# rpiInterface2.net
KiCad netlist of a schematic drawn in EAGLE
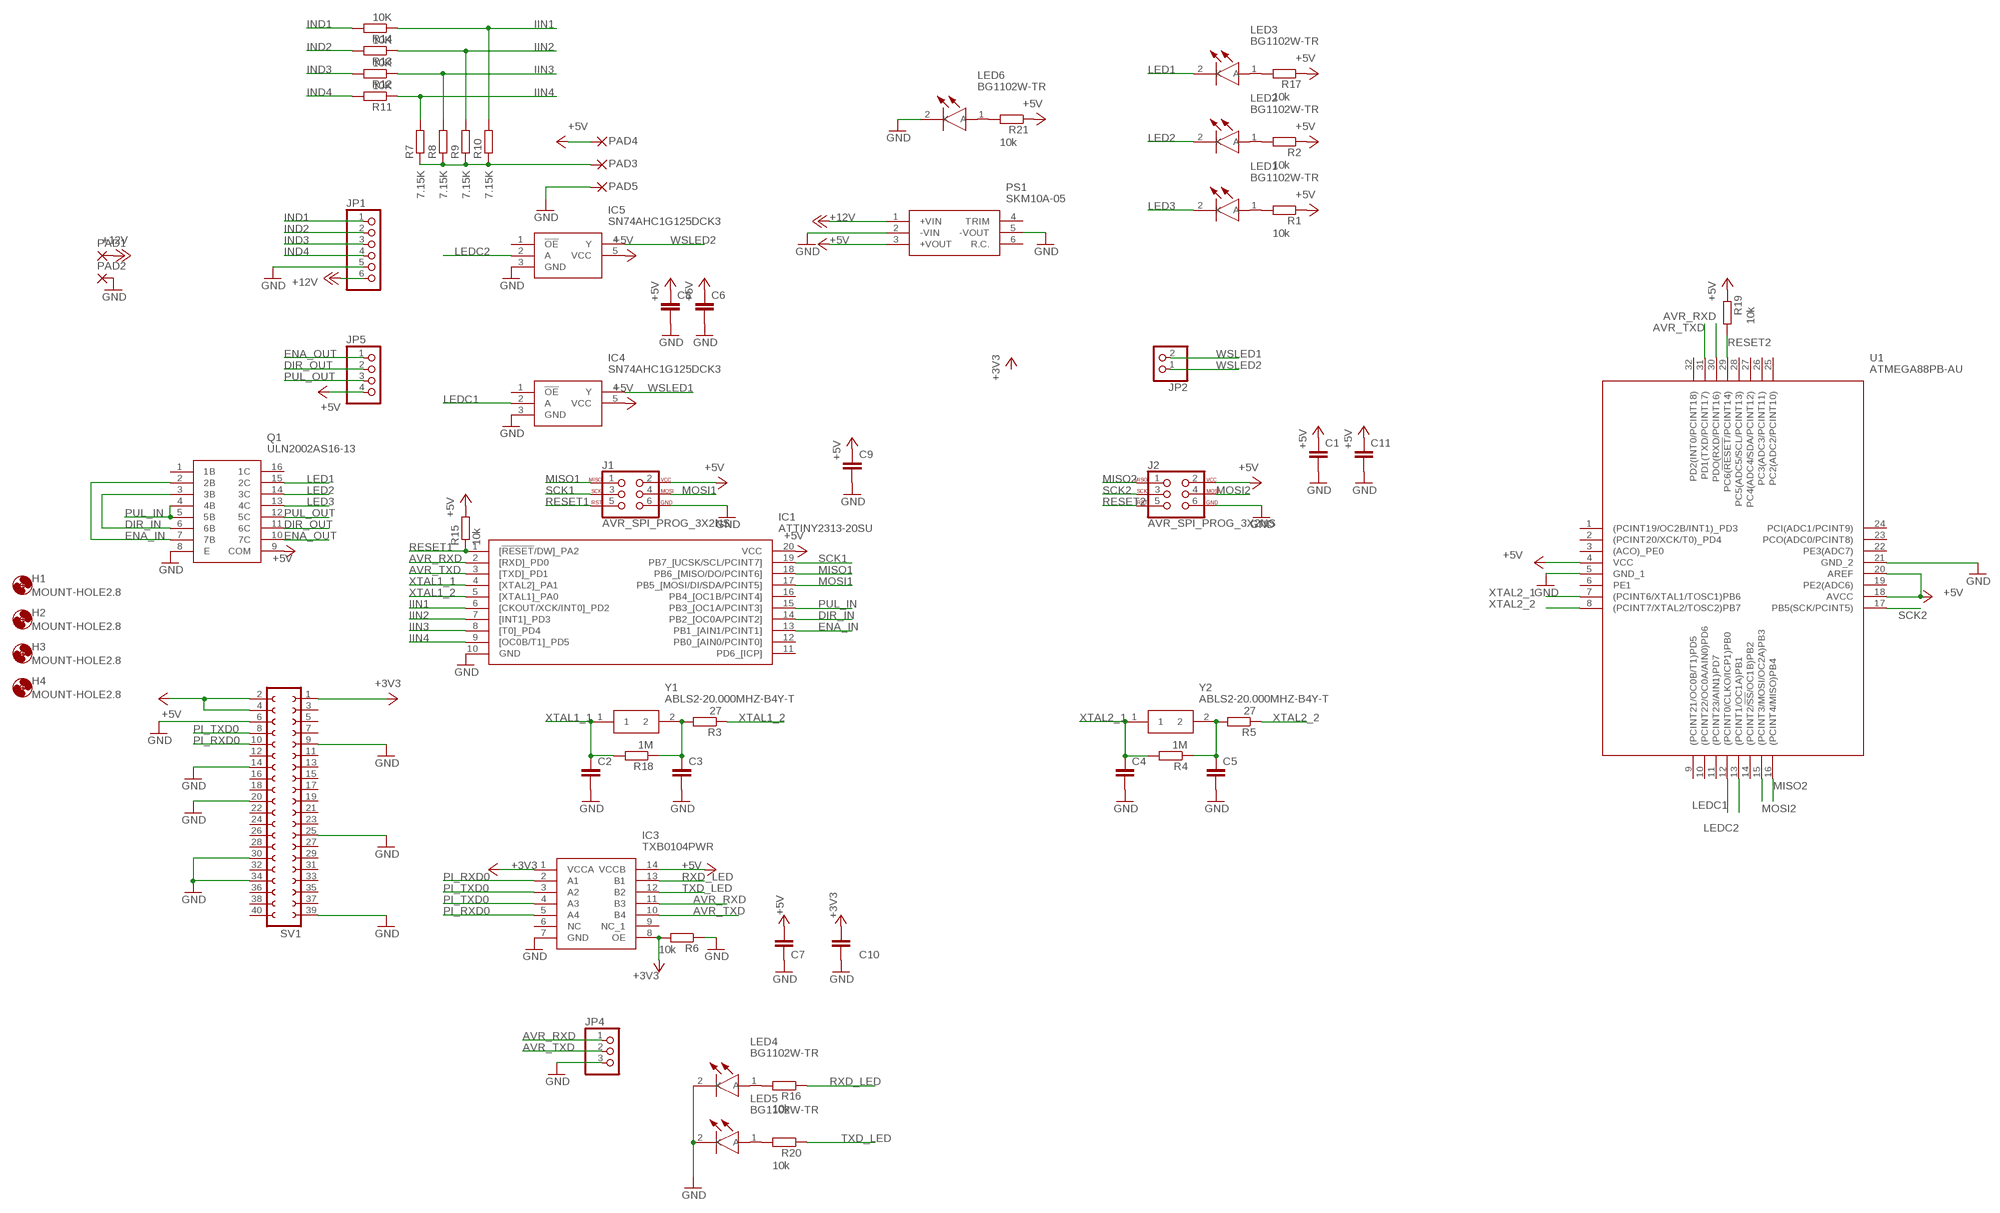
[diagram p0: schematic, sheet 1]

(export (version "E")
  (design (tool "Eeschema 10.0.6"))
  (components
    (comp (ref "C1")
      (value "C-EUC1206")
      (footprint "eagle-import:C1206")
      (libsource (lib "eagle-import") (part "C-EUC1206"))
    )
    (comp (ref "C2")
      (value "C-EUC1206")
      (footprint "eagle-import:C1206")
      (libsource (lib "eagle-import") (part "C-EUC1206"))
    )
    (comp (ref "C3")
      (value "C-EUC1206")
      (footprint "eagle-import:C1206")
      (libsource (lib "eagle-import") (part "C-EUC1206"))
    )
    (comp (ref "C4")
      (value "C-EUC1206")
      (footprint "eagle-import:C1206")
      (libsource (lib "eagle-import") (part "C-EUC1206"))
    )
    (comp (ref "C5")
      (value "C-EUC1206")
      (footprint "eagle-import:C1206")
      (libsource (lib "eagle-import") (part "C-EUC1206"))
    )
    (comp (ref "C6")
      (value "C-EUC1206")
      (footprint "eagle-import:C1206")
      (libsource (lib "eagle-import") (part "C-EUC1206"))
    )
    (comp (ref "C7")
      (value "C-EUC1206")
      (footprint "eagle-import:C1206")
      (libsource (lib "eagle-import") (part "C-EUC1206"))
    )
    (comp (ref "C8")
      (value "C-EUC1206")
      (footprint "eagle-import:C1206")
      (libsource (lib "eagle-import") (part "C-EUC1206"))
    )
    (comp (ref "C9")
      (value "C-EUC1206")
      (footprint "eagle-import:C1206")
      (libsource (lib "eagle-import") (part "C-EUC1206"))
    )
    (comp (ref "C10")
      (value "C-EUC1206")
      (footprint "eagle-import:C1206")
      (libsource (lib "eagle-import") (part "C-EUC1206"))
    )
    (comp (ref "C11")
      (value "C-EUC1206")
      (footprint "eagle-import:C1206")
      (libsource (lib "eagle-import") (part "C-EUC1206"))
    )
    (comp (ref "H1")
      (value "MOUNT-HOLE2.8")
      (footprint "eagle-import:2,8")
      (libsource (lib "eagle-import") (part "MOUNT-HOLE2.8"))
    )
    (comp (ref "H2")
      (value "MOUNT-HOLE2.8")
      (footprint "eagle-import:2,8")
      (libsource (lib "eagle-import") (part "MOUNT-HOLE2.8"))
    )
    (comp (ref "H3")
      (value "MOUNT-HOLE2.8")
      (footprint "eagle-import:2,8")
      (libsource (lib "eagle-import") (part "MOUNT-HOLE2.8"))
    )
    (comp (ref "H4")
      (value "MOUNT-HOLE2.8")
      (footprint "eagle-import:2,8")
      (libsource (lib "eagle-import") (part "MOUNT-HOLE2.8"))
    )
    (comp (ref "IC1")
      (value "ATTINY2313-20SU")
      (footprint "eagle-import:SOIC127P1032X265-20N")
      (fields (field (name "MOUSER_PART_NUMBER") "556-ATTINY2313-20SU"))
      (libsource (lib "eagle-import") (part "ATTINY2313-20SU"))
    )
    (comp (ref "IC3")
      (value "TXB0104PWR")
      (footprint "eagle-import:SOP65P640X120-14N")
      (fields (field (name "MOUSER_PART_NUMBER") "595-TXB0104PWR"))
      (libsource (lib "eagle-import") (part "TXB0104PWR"))
    )
    (comp (ref "IC4")
      (value "SN74AHC1G125DCK3")
      (footprint "eagle-import:SOT65P210X110-5N")
      (fields (field (name "MOUSER_PART_NUMBER") "595-SN74AHC1G125DCK3"))
      (libsource (lib "eagle-import") (part "SN74AHC1G125DCK3"))
    )
    (comp (ref "IC5")
      (value "SN74AHC1G125DCK3")
      (footprint "eagle-import:SOT65P210X110-5N")
      (fields (field (name "MOUSER_PART_NUMBER") "595-SN74AHC1G125DCK3"))
      (libsource (lib "eagle-import") (part "SN74AHC1G125DCK3"))
    )
    (comp (ref "J1")
      (value "AVR_SPI_PROG_3X2NS")
      (footprint "eagle-import:2X3-NS")
      (libsource (lib "eagle-import") (part "AVR_SPI_PROG_3X2NS"))
    )
    (comp (ref "J2")
      (value "AVR_SPI_PROG_3X2NS")
      (footprint "eagle-import:2X3-NS")
      (libsource (lib "eagle-import") (part "AVR_SPI_PROG_3X2NS"))
    )
    (comp (ref "JP1")
      (value "PINHD-1X6")
      (footprint "eagle-import:1X06")
      (libsource (lib "eagle-import") (part "PINHD-1X6"))
    )
    (comp (ref "JP2")
      (value "PINHD-1X2")
      (footprint "eagle-import:1X02")
      (libsource (lib "eagle-import") (part "PINHD-1X2"))
    )
    (comp (ref "JP4")
      (value "PINHD-1X3")
      (footprint "eagle-import:1X03")
      (libsource (lib "eagle-import") (part "PINHD-1X3"))
    )
    (comp (ref "JP5")
      (value "PINHD-1X4")
      (footprint "eagle-import:1X04")
      (libsource (lib "eagle-import") (part "PINHD-1X4"))
    )
    (comp (ref "LED1")
      (value "BG1102W-TR")
      (footprint "eagle-import:BG1102WTR")
      (fields (field (name "MOUSER_PART_NUMBER") "327-BG1102WTR"))
      (libsource (lib "eagle-import") (part "BG1102W-TR"))
    )
    (comp (ref "LED2")
      (value "BG1102W-TR")
      (footprint "eagle-import:BG1102WTR")
      (fields (field (name "MOUSER_PART_NUMBER") "327-BG1102WTR"))
      (libsource (lib "eagle-import") (part "BG1102W-TR"))
    )
    (comp (ref "LED3")
      (value "BG1102W-TR")
      (footprint "eagle-import:BG1102WTR")
      (fields (field (name "MOUSER_PART_NUMBER") "327-BG1102WTR"))
      (libsource (lib "eagle-import") (part "BG1102W-TR"))
    )
    (comp (ref "LED4")
      (value "BG1102W-TR")
      (footprint "eagle-import:BG1102WTR")
      (fields (field (name "MOUSER_PART_NUMBER") "327-BG1102WTR"))
      (libsource (lib "eagle-import") (part "BG1102W-TR"))
    )
    (comp (ref "LED5")
      (value "BG1102W-TR")
      (footprint "eagle-import:BG1102WTR")
      (fields (field (name "MOUSER_PART_NUMBER") "327-BG1102WTR"))
      (libsource (lib "eagle-import") (part "BG1102W-TR"))
    )
    (comp (ref "LED6")
      (value "BG1102W-TR")
      (footprint "eagle-import:BG1102WTR")
      (fields (field (name "MOUSER_PART_NUMBER") "327-BG1102WTR"))
      (libsource (lib "eagle-import") (part "BG1102W-TR"))
    )
    (comp (ref "PAD1")
      (value "3,17/1,3")
      (footprint "eagle-import:3,17_1,3")
      (libsource (lib "eagle-import") (part "3,17/1,3"))
    )
    (comp (ref "PAD2")
      (value "3,17/1,3")
      (footprint "eagle-import:3,17_1,3")
      (libsource (lib "eagle-import") (part "3,17/1,3"))
    )
    (comp (ref "PAD3")
      (value "SMD2")
      (footprint "eagle-import:SMD1,27-2,54")
      (libsource (lib "eagle-import") (part "SMD2"))
    )
    (comp (ref "PAD4")
      (value "SMD2")
      (footprint "eagle-import:SMD1,27-2,54")
      (libsource (lib "eagle-import") (part "SMD2"))
    )
    (comp (ref "PAD5")
      (value "SMD2")
      (footprint "eagle-import:SMD1,27-2,54")
      (libsource (lib "eagle-import") (part "SMD2"))
    )
    (comp (ref "PS1")
      (value "SKM10A-05")
      (footprint "eagle-import:SKM10A05")
      (fields (field (name "MOUSER_PART_NUMBER") "709-SKM10A-05"))
      (libsource (lib "eagle-import") (part "SKM10A-05"))
    )
    (comp (ref "Q1")
      (value "ULN2002AS16-13")
      (footprint "eagle-import:SOIC127P605X126-16N")
      (fields (field (name "MOUSER_PART_NUMBER") "621-ULN2002AS16-13"))
      (libsource (lib "eagle-import") (part "ULN2002AS16-13"))
    )
    (comp (ref "R1")
      (value "10k")
      (footprint "eagle-import:R1206")
      (libsource (lib "eagle-import") (part "R-EU_R1206"))
    )
    (comp (ref "R2")
      (value "10k")
      (footprint "eagle-import:R1206")
      (libsource (lib "eagle-import") (part "R-EU_R1206"))
    )
    (comp (ref "R3")
      (value "27")
      (footprint "eagle-import:R1206")
      (libsource (lib "eagle-import") (part "R-EU_R1206"))
    )
    (comp (ref "R4")
      (value "1M")
      (footprint "eagle-import:R1206")
      (libsource (lib "eagle-import") (part "R-EU_R1206"))
    )
    (comp (ref "R5")
      (value "27")
      (footprint "eagle-import:R1206")
      (libsource (lib "eagle-import") (part "R-EU_R1206"))
    )
    (comp (ref "R6")
      (value "10k")
      (footprint "eagle-import:R1206")
      (libsource (lib "eagle-import") (part "R-EU_R1206"))
    )
    (comp (ref "R7")
      (value "7.15K")
      (footprint "eagle-import:R1206")
      (libsource (lib "eagle-import") (part "R-EU_R1206"))
    )
    (comp (ref "R8")
      (value "7.15K")
      (footprint "eagle-import:R1206")
      (libsource (lib "eagle-import") (part "R-EU_R1206"))
    )
    (comp (ref "R9")
      (value "7.15K")
      (footprint "eagle-import:R1206")
      (libsource (lib "eagle-import") (part "R-EU_R1206"))
    )
    (comp (ref "R10")
      (value "7.15K")
      (footprint "eagle-import:R1206")
      (libsource (lib "eagle-import") (part "R-EU_R1206"))
    )
    (comp (ref "R11")
      (value "10K")
      (footprint "eagle-import:R1206")
      (libsource (lib "eagle-import") (part "R-EU_R1206"))
    )
    (comp (ref "R12")
      (value "10K")
      (footprint "eagle-import:R1206")
      (libsource (lib "eagle-import") (part "R-EU_R1206"))
    )
    (comp (ref "R13")
      (value "10K")
      (footprint "eagle-import:R1206")
      (libsource (lib "eagle-import") (part "R-EU_R1206"))
    )
    (comp (ref "R14")
      (value "10K")
      (footprint "eagle-import:R1206")
      (libsource (lib "eagle-import") (part "R-EU_R1206"))
    )
    (comp (ref "R15")
      (value "10k")
      (footprint "eagle-import:R1206")
      (libsource (lib "eagle-import") (part "R-EU_R1206"))
    )
    (comp (ref "R16")
      (value "10k")
      (footprint "eagle-import:R1206")
      (libsource (lib "eagle-import") (part "R-EU_R1206"))
    )
    (comp (ref "R17")
      (value "10k")
      (footprint "eagle-import:R1206")
      (libsource (lib "eagle-import") (part "R-EU_R1206"))
    )
    (comp (ref "R18")
      (value "1M")
      (footprint "eagle-import:R1206")
      (libsource (lib "eagle-import") (part "R-EU_R1206"))
    )
    (comp (ref "R19")
      (value "10k")
      (footprint "eagle-import:R1206")
      (libsource (lib "eagle-import") (part "R-EU_R1206"))
    )
    (comp (ref "R20")
      (value "10k")
      (footprint "eagle-import:R1206")
      (libsource (lib "eagle-import") (part "R-EU_R1206"))
    )
    (comp (ref "R21")
      (value "10k")
      (footprint "eagle-import:R1206")
      (libsource (lib "eagle-import") (part "R-EU_R1206"))
    )
    (comp (ref "SV1")
      (value "FE20-2")
      (footprint "eagle-import:FE20-2")
      (libsource (lib "eagle-import") (part "FE20-2"))
    )
    (comp (ref "U1")
      (value "ATMEGA88PB-AU")
      (footprint "eagle-import:QFP80P900X900X120-32N")
      (fields (field (name "MOUSER_PART_NUMBER") "556-ATMEGA88PB-AU"))
      (libsource (lib "eagle-import") (part "ATMEGA88PB-AU"))
    )
    (comp (ref "Y1")
      (value "ABLS2-20.000MHZ-B4Y-T")
      (footprint "eagle-import:HC_49US-(AT49)_1")
      (fields
        (field (name "MANUFACTURER_PART_NUMBER") "ABLS2-20.000MHz-B4Y-T")
        (field (name "MOUSER_PART_NUMBER") "815-ABLS2-20-B4YT")
      )
      (libsource (lib "eagle-import") (part "ABLS2-20.000MHZ-B4Y-T"))
    )
    (comp (ref "Y2")
      (value "ABLS2-20.000MHZ-B4Y-T")
      (footprint "eagle-import:HC_49US-(AT49)_1")
      (fields
        (field (name "MANUFACTURER_PART_NUMBER") "ABLS2-20.000MHz-B4Y-T")
        (field (name "MOUSER_PART_NUMBER") "815-ABLS2-20-B4YT")
      )
      (libsource (lib "eagle-import") (part "ABLS2-20.000MHZ-B4Y-T"))
    )
  )
  (nets
    (net (code "1") (name "+3V3") (class "Default")
      (node (ref "C10") (pin "1") (pinfunction "1_1") (pintype "passive"))
      (node (ref "IC3") (pin "1") (pinfunction "VCCA_1") (pintype "power_in"))
      (node (ref "IC3") (pin "8") (pinfunction "OE_8") (pintype "bidirectional"))
      (node (ref "R6") (pin "2") (pinfunction "2_2") (pintype "passive"))
      (node (ref "SV1") (pin "1") (pinfunction "1_1") (pintype "passive"))
    )
    (net (code "2") (name "+5V") (class "Default")
      (node (ref "C1") (pin "1") (pinfunction "1_1") (pintype "passive"))
      (node (ref "C11") (pin "1") (pinfunction "1_1") (pintype "passive"))
      (node (ref "C6") (pin "1") (pinfunction "1_1") (pintype "passive"))
      (node (ref "C7") (pin "1") (pinfunction "1_1") (pintype "passive"))
      (node (ref "C8") (pin "1") (pinfunction "1_1") (pintype "passive"))
      (node (ref "C9") (pin "1") (pinfunction "1_1") (pintype "passive"))
      (node (ref "IC1") (pin "20") (pinfunction "VCC_20") (pintype "power_in"))
      (node (ref "IC3") (pin "14") (pinfunction "VCCB_14") (pintype "power_in"))
      (node (ref "IC4") (pin "5") (pinfunction "VCC_5") (pintype "bidirectional"))
      (node (ref "IC5") (pin "5") (pinfunction "VCC_5") (pintype "bidirectional"))
      (node (ref "J1") (pin "2") (pinfunction "2_2") (pintype "passive"))
      (node (ref "J2") (pin "2") (pinfunction "2_2") (pintype "passive"))
      (node (ref "JP5") (pin "4") (pinfunction "4_4") (pintype "passive"))
      (node (ref "PAD4") (pin "1") (pinfunction "P_1") (pintype "passive"))
      (node (ref "PS1") (pin "3") (pinfunction "+VOUT_3") (pintype "bidirectional"))
      (node (ref "Q1") (pin "9") (pinfunction "COM_9") (pintype "bidirectional"))
      (node (ref "R1") (pin "1") (pinfunction "1_1") (pintype "passive"))
      (node (ref "R15") (pin "2") (pinfunction "2_2") (pintype "passive"))
      (node (ref "R17") (pin "1") (pinfunction "1_1") (pintype "passive"))
      (node (ref "R19") (pin "1") (pinfunction "1_1") (pintype "passive"))
      (node (ref "R2") (pin "1") (pinfunction "1_1") (pintype "passive"))
      (node (ref "R21") (pin "1") (pinfunction "1_1") (pintype "passive"))
      (node (ref "SV1") (pin "2") (pinfunction "2_2") (pintype "passive"))
      (node (ref "SV1") (pin "4") (pinfunction "4_4") (pintype "passive"))
      (node (ref "U1") (pin "18") (pinfunction "AVCC_18") (pintype "power_in"))
      (node (ref "U1") (pin "20") (pinfunction "AREF_20") (pintype "power_in"))
      (node (ref "U1") (pin "4") (pinfunction "VCC_4") (pintype "power_in"))
    )
    (net (code "3") (name "+12V") (class "Default")
      (node (ref "JP1") (pin "6") (pinfunction "6_6") (pintype "passive"))
      (node (ref "PAD1") (pin "1") (pinfunction "P_1") (pintype "passive"))
      (node (ref "PS1") (pin "1") (pinfunction "+VIN_1") (pintype "bidirectional"))
    )
    (net (code "4") (name "/AVR_RXD") (class "Default")
      (node (ref "IC1") (pin "2") (pinfunction "[RXD]_PD0_2") (pintype "bidirectional"))
      (node (ref "IC3") (pin "11") (pinfunction "B3_11") (pintype "bidirectional"))
      (node (ref "JP4") (pin "1") (pinfunction "1_1") (pintype "passive"))
      (node (ref "U1") (pin "30") (pinfunction "PDO(RXD/PCINT16)_30") (pintype "bidirectional"))
    )
    (net (code "5") (name "/AVR_TXD") (class "Default")
      (node (ref "IC1") (pin "3") (pinfunction "[TXD]_PD1_3") (pintype "bidirectional"))
      (node (ref "IC3") (pin "10") (pinfunction "B4_10") (pintype "bidirectional"))
      (node (ref "JP4") (pin "2") (pinfunction "2_2") (pintype "passive"))
      (node (ref "U1") (pin "31") (pinfunction "PD1(TXD/PCINT17)_31") (pintype "bidirectional"))
    )
    (net (code "6") (name "/DIR_IN") (class "Default")
      (node (ref "IC1") (pin "14") (pinfunction "PB2_[OC0A/PCINT2]_14") (pintype "input"))
      (node (ref "Q1") (pin "3") (pinfunction "3B_3") (pintype "bidirectional"))
      (node (ref "Q1") (pin "6") (pinfunction "6B_6") (pintype "bidirectional"))
    )
    (net (code "7") (name "/DIR_OUT") (class "Default")
      (node (ref "JP5") (pin "2") (pinfunction "2_2") (pintype "passive"))
      (node (ref "Q1") (pin "11") (pinfunction "6C_11") (pintype "bidirectional"))
    )
    (net (code "8") (name "/ENA_IN") (class "Default")
      (node (ref "IC1") (pin "13") (pinfunction "PB1_[AIN1/PCINT1]_13") (pintype "input"))
      (node (ref "Q1") (pin "2") (pinfunction "2B_2") (pintype "bidirectional"))
      (node (ref "Q1") (pin "7") (pinfunction "7B_7") (pintype "bidirectional"))
    )
    (net (code "9") (name "/ENA_OUT") (class "Default")
      (node (ref "JP5") (pin "1") (pinfunction "1_1") (pintype "passive"))
      (node (ref "Q1") (pin "10") (pinfunction "7C_10") (pintype "bidirectional"))
    )
    (net (code "10") (name "/IIN1") (class "Default")
      (node (ref "IC1") (pin "6") (pinfunction "[CKOUT/XCK/INT0]_PD2_6") (pintype "output"))
      (node (ref "R10") (pin "2") (pinfunction "2_2") (pintype "passive"))
      (node (ref "R14") (pin "1") (pinfunction "1_1") (pintype "passive"))
    )
    (net (code "11") (name "/IIN2") (class "Default")
      (node (ref "IC1") (pin "7") (pinfunction "[INT1]_PD3_7") (pintype "input"))
      (node (ref "R13") (pin "1") (pinfunction "1_1") (pintype "passive"))
      (node (ref "R9") (pin "2") (pinfunction "2_2") (pintype "passive"))
    )
    (net (code "12") (name "/IIN3") (class "Default")
      (node (ref "IC1") (pin "8") (pinfunction "[T0]_PD4_8") (pintype "bidirectional"))
      (node (ref "R12") (pin "1") (pinfunction "1_1") (pintype "passive"))
      (node (ref "R8") (pin "2") (pinfunction "2_2") (pintype "passive"))
    )
    (net (code "13") (name "/IIN4") (class "Default")
      (node (ref "IC1") (pin "9") (pinfunction "[OC0B/T1]_PD5_9") (pintype "bidirectional"))
      (node (ref "R11") (pin "1") (pinfunction "1_1") (pintype "passive"))
      (node (ref "R7") (pin "2") (pinfunction "2_2") (pintype "passive"))
    )
    (net (code "14") (name "/IND1") (class "Default")
      (node (ref "JP1") (pin "1") (pinfunction "1_1") (pintype "passive"))
      (node (ref "R14") (pin "2") (pinfunction "2_2") (pintype "passive"))
    )
    (net (code "15") (name "/IND2") (class "Default")
      (node (ref "JP1") (pin "2") (pinfunction "2_2") (pintype "passive"))
      (node (ref "R13") (pin "2") (pinfunction "2_2") (pintype "passive"))
    )
    (net (code "16") (name "/IND3") (class "Default")
      (node (ref "JP1") (pin "3") (pinfunction "3_3") (pintype "passive"))
      (node (ref "R12") (pin "2") (pinfunction "2_2") (pintype "passive"))
    )
    (net (code "17") (name "/IND4") (class "Default")
      (node (ref "JP1") (pin "4") (pinfunction "4_4") (pintype "passive"))
      (node (ref "R11") (pin "2") (pinfunction "2_2") (pintype "passive"))
    )
    (net (code "18") (name "/LED1") (class "Default")
      (node (ref "LED3") (pin "2") (pinfunction "K_2") (pintype "bidirectional"))
      (node (ref "Q1") (pin "15") (pinfunction "2C_15") (pintype "bidirectional"))
    )
    (net (code "19") (name "/LED2") (class "Default")
      (node (ref "LED2") (pin "2") (pinfunction "K_2") (pintype "bidirectional"))
      (node (ref "Q1") (pin "14") (pinfunction "3C_14") (pintype "bidirectional"))
    )
    (net (code "20") (name "/LED3") (class "Default")
      (node (ref "LED1") (pin "2") (pinfunction "K_2") (pintype "bidirectional"))
      (node (ref "Q1") (pin "13") (pinfunction "4C_13") (pintype "bidirectional"))
    )
    (net (code "21") (name "/LEDC1") (class "Default")
      (node (ref "IC4") (pin "2") (pinfunction "A_2") (pintype "bidirectional"))
      (node (ref "U1") (pin "12") (pinfunction "(PCINT0/CLKO/ICP1)PB0_12") (pintype "bidirectional"))
    )
    (net (code "22") (name "/LEDC2") (class "Default")
      (node (ref "IC5") (pin "2") (pinfunction "A_2") (pintype "bidirectional"))
      (node (ref "U1") (pin "13") (pinfunction "(PCINT1/OC1A)PB1_13") (pintype "bidirectional"))
    )
    (net (code "23") (name "/MISO1") (class "Default")
      (node (ref "IC1") (pin "18") (pinfunction "PB6_[MISO/DO/PCINT6]_18") (pintype "input"))
      (node (ref "J1") (pin "1") (pinfunction "1_1") (pintype "passive"))
    )
    (net (code "24") (name "/MISO2") (class "Default")
      (node (ref "J2") (pin "1") (pinfunction "1_1") (pintype "passive"))
      (node (ref "U1") (pin "16") (pinfunction "(PCINT4/MISO)PB4_16") (pintype "bidirectional"))
    )
    (net (code "25") (name "/MOSI1") (class "Default")
      (node (ref "IC1") (pin "17") (pinfunction "PB5_[MOSI/DI/SDA/PCINT5]_17") (pintype "input"))
      (node (ref "J1") (pin "4") (pinfunction "4_4") (pintype "passive"))
    )
    (net (code "26") (name "/MOSI2") (class "Default")
      (node (ref "J2") (pin "4") (pinfunction "4_4") (pintype "passive"))
      (node (ref "U1") (pin "15") (pinfunction "(PCINT3/MOSI/OC2A)PB3_15") (pintype "bidirectional"))
    )
    (net (code "27") (name "/PI_RXD0") (class "Default")
      (node (ref "IC3") (pin "2") (pinfunction "A1_2") (pintype "bidirectional"))
      (node (ref "IC3") (pin "5") (pinfunction "A4_5") (pintype "bidirectional"))
      (node (ref "SV1") (pin "10") (pinfunction "10_10") (pintype "passive"))
    )
    (net (code "28") (name "/PI_TXD0") (class "Default")
      (node (ref "IC3") (pin "3") (pinfunction "A2_3") (pintype "bidirectional"))
      (node (ref "IC3") (pin "4") (pinfunction "A3_4") (pintype "bidirectional"))
      (node (ref "SV1") (pin "8") (pinfunction "8_8") (pintype "passive"))
    )
    (net (code "29") (name "/PUL_IN") (class "Default")
      (node (ref "IC1") (pin "15") (pinfunction "PB3_[OC1A/PCINT3]_15") (pintype "input"))
      (node (ref "Q1") (pin "4") (pinfunction "4B_4") (pintype "bidirectional"))
      (node (ref "Q1") (pin "5") (pinfunction "5B_5") (pintype "bidirectional"))
    )
    (net (code "30") (name "/PUL_OUT") (class "Default")
      (node (ref "JP5") (pin "3") (pinfunction "3_3") (pintype "passive"))
      (node (ref "Q1") (pin "12") (pinfunction "5C_12") (pintype "bidirectional"))
    )
    (net (code "31") (name "/RESET1") (class "Default")
      (node (ref "IC1") (pin "1") (pinfunction "[~{RESET}/DW]_PA2_1") (pintype "bidirectional"))
      (node (ref "J1") (pin "5") (pinfunction "5_5") (pintype "passive"))
      (node (ref "R15") (pin "1") (pinfunction "1_1") (pintype "passive"))
    )
    (net (code "32") (name "/RESET2") (class "Default")
      (node (ref "J2") (pin "5") (pinfunction "5_5") (pintype "passive"))
      (node (ref "R19") (pin "2") (pinfunction "2_2") (pintype "passive"))
      (node (ref "U1") (pin "29") (pinfunction "PC6(~{RESET}/PCINT14)_29") (pintype "bidirectional"))
    )
    (net (code "33") (name "/RXD_LED") (class "Default")
      (node (ref "IC3") (pin "13") (pinfunction "B1_13") (pintype "bidirectional"))
      (node (ref "R16") (pin "1") (pinfunction "1_1") (pintype "passive"))
    )
    (net (code "34") (name "/SCK1") (class "Default")
      (node (ref "IC1") (pin "19") (pinfunction "PB7_[UCSK/SCL/PCINT7]_19") (pintype "input"))
      (node (ref "J1") (pin "3") (pinfunction "3_3") (pintype "passive"))
    )
    (net (code "35") (name "/SCK2") (class "Default")
      (node (ref "J2") (pin "3") (pinfunction "3_3") (pintype "passive"))
      (node (ref "U1") (pin "17") (pinfunction "PB5(SCK/PCINT5)_17") (pintype "bidirectional"))
    )
    (net (code "36") (name "/TXD_LED") (class "Default")
      (node (ref "IC3") (pin "12") (pinfunction "B2_12") (pintype "bidirectional"))
      (node (ref "R20") (pin "1") (pinfunction "1_1") (pintype "passive"))
    )
    (net (code "37") (name "/WSLED1") (class "Default")
      (node (ref "IC4") (pin "4") (pinfunction "Y_4") (pintype "bidirectional"))
      (node (ref "JP2") (pin "2") (pinfunction "2_2") (pintype "passive"))
    )
    (net (code "38") (name "/WSLED2") (class "Default")
      (node (ref "IC5") (pin "4") (pinfunction "Y_4") (pintype "bidirectional"))
      (node (ref "JP2") (pin "1") (pinfunction "1_1") (pintype "passive"))
    )
    (net (code "39") (name "/XTAL1_1") (class "Default")
      (node (ref "C2") (pin "1") (pinfunction "1_1") (pintype "passive"))
      (node (ref "IC1") (pin "4") (pinfunction "[XTAL2]_PA1_4") (pintype "bidirectional"))
      (node (ref "R18") (pin "2") (pinfunction "2_2") (pintype "passive"))
      (node (ref "Y1") (pin "1") (pinfunction "1_1") (pintype "bidirectional"))
    )
    (net (code "40") (name "/XTAL1_2") (class "Default")
      (node (ref "IC1") (pin "5") (pinfunction "[XTAL1]_PA0_5") (pintype "bidirectional"))
      (node (ref "R3") (pin "1") (pinfunction "1_1") (pintype "passive"))
    )
    (net (code "41") (name "/XTAL2_1") (class "Default")
      (node (ref "C4") (pin "1") (pinfunction "1_1") (pintype "passive"))
      (node (ref "R4") (pin "2") (pinfunction "2_2") (pintype "passive"))
      (node (ref "U1") (pin "7") (pinfunction "(PCINT6/XTAL1/TOSC1)PB6_7") (pintype "bidirectional"))
      (node (ref "Y2") (pin "1") (pinfunction "1_1") (pintype "bidirectional"))
    )
    (net (code "42") (name "/XTAL2_2") (class "Default")
      (node (ref "R5") (pin "1") (pinfunction "1_1") (pintype "passive"))
      (node (ref "U1") (pin "8") (pinfunction "(PCINT7/XTAL2/TOSC2)PB7_8") (pintype "bidirectional"))
    )
    (net (code "43") (name "GND") (class "Default")
      (node (ref "C1") (pin "2") (pinfunction "2_2") (pintype "passive"))
      (node (ref "C10") (pin "2") (pinfunction "2_2") (pintype "passive"))
      (node (ref "C11") (pin "2") (pinfunction "2_2") (pintype "passive"))
      (node (ref "C2") (pin "2") (pinfunction "2_2") (pintype "passive"))
      (node (ref "C3") (pin "2") (pinfunction "2_2") (pintype "passive"))
      (node (ref "C4") (pin "2") (pinfunction "2_2") (pintype "passive"))
      (node (ref "C5") (pin "2") (pinfunction "2_2") (pintype "passive"))
      (node (ref "C6") (pin "2") (pinfunction "2_2") (pintype "passive"))
      (node (ref "C7") (pin "2") (pinfunction "2_2") (pintype "passive"))
      (node (ref "C8") (pin "2") (pinfunction "2_2") (pintype "passive"))
      (node (ref "C9") (pin "2") (pinfunction "2_2") (pintype "passive"))
      (node (ref "IC1") (pin "10") (pinfunction "GND_10") (pintype "power_in"))
      (node (ref "IC3") (pin "7") (pinfunction "GND_7") (pintype "power_in"))
      (node (ref "IC4") (pin "3") (pinfunction "GND_3") (pintype "bidirectional"))
      (node (ref "IC5") (pin "3") (pinfunction "GND_3") (pintype "bidirectional"))
      (node (ref "J1") (pin "6") (pinfunction "6_6") (pintype "passive"))
      (node (ref "J2") (pin "6") (pinfunction "6_6") (pintype "passive"))
      (node (ref "JP1") (pin "5") (pinfunction "5_5") (pintype "passive"))
      (node (ref "JP4") (pin "3") (pinfunction "3_3") (pintype "passive"))
      (node (ref "LED4") (pin "2") (pinfunction "K_2") (pintype "bidirectional"))
      (node (ref "LED5") (pin "2") (pinfunction "K_2") (pintype "bidirectional"))
      (node (ref "LED6") (pin "2") (pinfunction "K_2") (pintype "bidirectional"))
      (node (ref "PAD2") (pin "1") (pinfunction "P_1") (pintype "passive"))
      (node (ref "PAD5") (pin "1") (pinfunction "P_1") (pintype "passive"))
      (node (ref "PS1") (pin "2") (pinfunction "-VIN_2") (pintype "bidirectional"))
      (node (ref "PS1") (pin "5") (pinfunction "-VOUT_5") (pintype "bidirectional"))
      (node (ref "Q1") (pin "8") (pinfunction "E_8") (pintype "bidirectional"))
      (node (ref "R6") (pin "1") (pinfunction "1_1") (pintype "passive"))
      (node (ref "SV1") (pin "14") (pinfunction "14_14") (pintype "passive"))
      (node (ref "SV1") (pin "20") (pinfunction "20_20") (pintype "passive"))
      (node (ref "SV1") (pin "25") (pinfunction "25_25") (pintype "passive"))
      (node (ref "SV1") (pin "30") (pinfunction "30_30") (pintype "passive"))
      (node (ref "SV1") (pin "34") (pinfunction "34_34") (pintype "passive"))
      (node (ref "SV1") (pin "39") (pinfunction "39_39") (pintype "passive"))
      (node (ref "SV1") (pin "6") (pinfunction "6_6") (pintype "passive"))
      (node (ref "SV1") (pin "9") (pinfunction "9_9") (pintype "passive"))
      (node (ref "U1") (pin "21") (pinfunction "GND_2_21") (pintype "power_in"))
      (node (ref "U1") (pin "5") (pinfunction "GND_1_5") (pintype "power_in"))
    )
    (net (code "44") (name "Net-(C3-Pad1)") (class "Default")
      (node (ref "C3") (pin "1") (pinfunction "1_1") (pintype "passive"))
      (node (ref "R18") (pin "1") (pinfunction "1_1") (pintype "passive"))
      (node (ref "R3") (pin "2") (pinfunction "2_2") (pintype "passive"))
      (node (ref "Y1") (pin "2") (pinfunction "2_2") (pintype "bidirectional"))
    )
    (net (code "45") (name "Net-(C5-Pad1)") (class "Default")
      (node (ref "C5") (pin "1") (pinfunction "1_1") (pintype "passive"))
      (node (ref "R4") (pin "1") (pinfunction "1_1") (pintype "passive"))
      (node (ref "R5") (pin "2") (pinfunction "2_2") (pintype "passive"))
      (node (ref "Y2") (pin "2") (pinfunction "2_2") (pintype "bidirectional"))
    )
    (net (code "46") (name "Net-(LED1-A)") (class "Default")
      (node (ref "LED1") (pin "1") (pinfunction "A_1") (pintype "bidirectional"))
      (node (ref "R1") (pin "2") (pinfunction "2_2") (pintype "passive"))
    )
    (net (code "47") (name "Net-(LED2-A)") (class "Default")
      (node (ref "LED2") (pin "1") (pinfunction "A_1") (pintype "bidirectional"))
      (node (ref "R2") (pin "2") (pinfunction "2_2") (pintype "passive"))
    )
    (net (code "48") (name "Net-(LED3-A)") (class "Default")
      (node (ref "LED3") (pin "1") (pinfunction "A_1") (pintype "bidirectional"))
      (node (ref "R17") (pin "2") (pinfunction "2_2") (pintype "passive"))
    )
    (net (code "49") (name "Net-(LED4-A)") (class "Default")
      (node (ref "LED4") (pin "1") (pinfunction "A_1") (pintype "bidirectional"))
      (node (ref "R16") (pin "2") (pinfunction "2_2") (pintype "passive"))
    )
    (net (code "50") (name "Net-(LED5-A)") (class "Default")
      (node (ref "LED5") (pin "1") (pinfunction "A_1") (pintype "bidirectional"))
      (node (ref "R20") (pin "2") (pinfunction "2_2") (pintype "passive"))
    )
    (net (code "51") (name "Net-(LED6-A)") (class "Default")
      (node (ref "LED6") (pin "1") (pinfunction "A_1") (pintype "bidirectional"))
      (node (ref "R21") (pin "2") (pinfunction "2_2") (pintype "passive"))
    )
    (net (code "52") (name "Net-(PAD3-P)") (class "Default")
      (node (ref "PAD3") (pin "1") (pinfunction "P_1") (pintype "passive"))
      (node (ref "R10") (pin "1") (pinfunction "1_1") (pintype "passive"))
      (node (ref "R7") (pin "1") (pinfunction "1_1") (pintype "passive"))
      (node (ref "R8") (pin "1") (pinfunction "1_1") (pintype "passive"))
      (node (ref "R9") (pin "1") (pinfunction "1_1") (pintype "passive"))
    )
    (net (code "53") (name "unconnected-(IC1-PB0_[AIN0{slash}PCINT0]-Pad12)") (class "Default")
      (node (ref "IC1") (pin "12") (pinfunction "PB0_[AIN0/PCINT0]_12") (pintype "input"))
    )
    (net (code "54") (name "unconnected-(IC1-PB4_[OC1B{slash}PCINT4]-Pad16)") (class "Default")
      (node (ref "IC1") (pin "16") (pinfunction "PB4_[OC1B/PCINT4]_16") (pintype "input"))
    )
    (net (code "55") (name "unconnected-(IC1-PD6_[ICP]-Pad11)") (class "Default")
      (node (ref "IC1") (pin "11") (pinfunction "PD6_[ICP]_11") (pintype "bidirectional"))
    )
    (net (code "56") (name "unconnected-(IC3-NC-Pad6)") (class "Default")
      (node (ref "IC3") (pin "6") (pinfunction "NC_6") (pintype "no_connect"))
    )
    (net (code "57") (name "unconnected-(IC3-NC_1-Pad9)") (class "Default")
      (node (ref "IC3") (pin "9") (pinfunction "NC_1_9") (pintype "bidirectional"))
    )
    (net (code "58") (name "unconnected-(IC4-~{OE}-Pad1)") (class "Default")
      (node (ref "IC4") (pin "1") (pinfunction "~{OE}_1") (pintype "bidirectional"))
    )
    (net (code "59") (name "unconnected-(IC5-~{OE}-Pad1)") (class "Default")
      (node (ref "IC5") (pin "1") (pinfunction "~{OE}_1") (pintype "bidirectional"))
    )
    (net (code "60") (name "unconnected-(PS1-R.C.-Pad6)") (class "Default")
      (node (ref "PS1") (pin "6") (pinfunction "R.C._6") (pintype "bidirectional"))
    )
    (net (code "61") (name "unconnected-(PS1-TRIM-Pad4)") (class "Default")
      (node (ref "PS1") (pin "4") (pinfunction "TRIM_4") (pintype "bidirectional"))
    )
    (net (code "62") (name "unconnected-(Q1-1B-Pad1)") (class "Default")
      (node (ref "Q1") (pin "1") (pinfunction "1B_1") (pintype "bidirectional"))
    )
    (net (code "63") (name "unconnected-(Q1-1C-Pad16)") (class "Default")
      (node (ref "Q1") (pin "16") (pinfunction "1C_16") (pintype "bidirectional"))
    )
    (net (code "64") (name "unconnected-(SV1-Pad3)") (class "Default")
      (node (ref "SV1") (pin "3") (pinfunction "3_3") (pintype "passive"))
    )
    (net (code "65") (name "unconnected-(SV1-Pad5)") (class "Default")
      (node (ref "SV1") (pin "5") (pinfunction "5_5") (pintype "passive"))
    )
    (net (code "66") (name "unconnected-(SV1-Pad7)") (class "Default")
      (node (ref "SV1") (pin "7") (pinfunction "7_7") (pintype "passive"))
    )
    (net (code "67") (name "unconnected-(SV1-Pad11)") (class "Default")
      (node (ref "SV1") (pin "11") (pinfunction "11_11") (pintype "passive"))
    )
    (net (code "68") (name "unconnected-(SV1-Pad12)") (class "Default")
      (node (ref "SV1") (pin "12") (pinfunction "12_12") (pintype "passive"))
    )
    (net (code "69") (name "unconnected-(SV1-Pad13)") (class "Default")
      (node (ref "SV1") (pin "13") (pinfunction "13_13") (pintype "passive"))
    )
    (net (code "70") (name "unconnected-(SV1-Pad15)") (class "Default")
      (node (ref "SV1") (pin "15") (pinfunction "15_15") (pintype "passive"))
    )
    (net (code "71") (name "unconnected-(SV1-Pad16)") (class "Default")
      (node (ref "SV1") (pin "16") (pinfunction "16_16") (pintype "passive"))
    )
    (net (code "72") (name "unconnected-(SV1-Pad17)") (class "Default")
      (node (ref "SV1") (pin "17") (pinfunction "17_17") (pintype "passive"))
    )
    (net (code "73") (name "unconnected-(SV1-Pad18)") (class "Default")
      (node (ref "SV1") (pin "18") (pinfunction "18_18") (pintype "passive"))
    )
    (net (code "74") (name "unconnected-(SV1-Pad19)") (class "Default")
      (node (ref "SV1") (pin "19") (pinfunction "19_19") (pintype "passive"))
    )
    (net (code "75") (name "unconnected-(SV1-Pad21)") (class "Default")
      (node (ref "SV1") (pin "21") (pinfunction "21_21") (pintype "passive"))
    )
    (net (code "76") (name "unconnected-(SV1-Pad22)") (class "Default")
      (node (ref "SV1") (pin "22") (pinfunction "22_22") (pintype "passive"))
    )
    (net (code "77") (name "unconnected-(SV1-Pad23)") (class "Default")
      (node (ref "SV1") (pin "23") (pinfunction "23_23") (pintype "passive"))
    )
    (net (code "78") (name "unconnected-(SV1-Pad24)") (class "Default")
      (node (ref "SV1") (pin "24") (pinfunction "24_24") (pintype "passive"))
    )
    (net (code "79") (name "unconnected-(SV1-Pad26)") (class "Default")
      (node (ref "SV1") (pin "26") (pinfunction "26_26") (pintype "passive"))
    )
    (net (code "80") (name "unconnected-(SV1-Pad27)") (class "Default")
      (node (ref "SV1") (pin "27") (pinfunction "27_27") (pintype "passive"))
    )
    (net (code "81") (name "unconnected-(SV1-Pad28)") (class "Default")
      (node (ref "SV1") (pin "28") (pinfunction "28_28") (pintype "passive"))
    )
    (net (code "82") (name "unconnected-(SV1-Pad29)") (class "Default")
      (node (ref "SV1") (pin "29") (pinfunction "29_29") (pintype "passive"))
    )
    (net (code "83") (name "unconnected-(SV1-Pad31)") (class "Default")
      (node (ref "SV1") (pin "31") (pinfunction "31_31") (pintype "passive"))
    )
    (net (code "84") (name "unconnected-(SV1-Pad32)") (class "Default")
      (node (ref "SV1") (pin "32") (pinfunction "32_32") (pintype "passive"))
    )
    (net (code "85") (name "unconnected-(SV1-Pad33)") (class "Default")
      (node (ref "SV1") (pin "33") (pinfunction "33_33") (pintype "passive"))
    )
    (net (code "86") (name "unconnected-(SV1-Pad35)") (class "Default")
      (node (ref "SV1") (pin "35") (pinfunction "35_35") (pintype "passive"))
    )
    (net (code "87") (name "unconnected-(SV1-Pad36)") (class "Default")
      (node (ref "SV1") (pin "36") (pinfunction "36_36") (pintype "passive"))
    )
    (net (code "88") (name "unconnected-(SV1-Pad37)") (class "Default")
      (node (ref "SV1") (pin "37") (pinfunction "37_37") (pintype "passive"))
    )
    (net (code "89") (name "unconnected-(SV1-Pad38)") (class "Default")
      (node (ref "SV1") (pin "38") (pinfunction "38_38") (pintype "passive"))
    )
    (net (code "90") (name "unconnected-(SV1-Pad40)") (class "Default")
      (node (ref "SV1") (pin "40") (pinfunction "40_40") (pintype "passive"))
    )
    (net (code "91") (name "unconnected-(U1-(ACO)_PE0-Pad3)") (class "Default")
      (node (ref "U1") (pin "3") (pinfunction "(ACO)_PE0_3") (pintype "bidirectional"))
    )
    (net (code "92") (name "unconnected-(U1-(PCINT2{slash}~{SS}{slash}OC1B)PB2-Pad14)") (class "Default")
      (node (ref "U1") (pin "14") (pinfunction "(PCINT2/~{SS}/OC1B)PB2_14") (pintype "bidirectional"))
    )
    (net (code "93") (name "unconnected-(U1-(PCINT19{slash}OC2B{slash}INT1)_PD3-Pad1)") (class "Default")
      (node (ref "U1") (pin "1") (pinfunction "(PCINT19/OC2B/INT1)_PD3_1") (pintype "bidirectional"))
    )
    (net (code "94") (name "unconnected-(U1-(PCINT20{slash}XCK{slash}T0)_PD4-Pad2)") (class "Default")
      (node (ref "U1") (pin "2") (pinfunction "(PCINT20/XCK/T0)_PD4_2") (pintype "bidirectional"))
    )
    (net (code "95") (name "unconnected-(U1-(PCINT21{slash}OC0B{slash}T1)PD5-Pad9)") (class "Default")
      (node (ref "U1") (pin "9") (pinfunction "(PCINT21/OC0B/T1)PD5_9") (pintype "bidirectional"))
    )
    (net (code "96") (name "unconnected-(U1-(PCINT22{slash}OC0A{slash}AIN0)PD6-Pad10)") (class "Default")
      (node (ref "U1") (pin "10") (pinfunction "(PCINT22/OC0A/AIN0)PD6_10") (pintype "bidirectional"))
    )
    (net (code "97") (name "unconnected-(U1-(PCINT23{slash}AIN1)PD7-Pad11)") (class "Default")
      (node (ref "U1") (pin "11") (pinfunction "(PCINT23/AIN1)PD7_11") (pintype "bidirectional"))
    )
    (net (code "98") (name "unconnected-(U1-PC2(ADC2{slash}PCINT10)-Pad25)") (class "Default")
      (node (ref "U1") (pin "25") (pinfunction "PC2(ADC2/PCINT10)_25") (pintype "bidirectional"))
    )
    (net (code "99") (name "unconnected-(U1-PC3(ADC3{slash}PCINT11)-Pad26)") (class "Default")
      (node (ref "U1") (pin "26") (pinfunction "PC3(ADC3/PCINT11)_26") (pintype "bidirectional"))
    )
    (net (code "100") (name "unconnected-(U1-PC4(ADC4{slash}SDA{slash}PCINT12)-Pad27)") (class "Default")
      (node (ref "U1") (pin "27") (pinfunction "PC4(ADC4/SDA/PCINT12)_27") (pintype "bidirectional"))
    )
    (net (code "101") (name "unconnected-(U1-PC5(ADC5{slash}SCL{slash}PCINT13)-Pad28)") (class "Default")
      (node (ref "U1") (pin "28") (pinfunction "PC5(ADC5/SCL/PCINT13)_28") (pintype "bidirectional"))
    )
    (net (code "102") (name "unconnected-(U1-PCI(ADC1{slash}PCINT9)-Pad24)") (class "Default")
      (node (ref "U1") (pin "24") (pinfunction "PCI(ADC1/PCINT9)_24") (pintype "bidirectional"))
    )
    (net (code "103") (name "unconnected-(U1-PCO(ADC0{slash}PCINT8)-Pad23)") (class "Default")
      (node (ref "U1") (pin "23") (pinfunction "PCO(ADC0/PCINT8)_23") (pintype "bidirectional"))
    )
    (net (code "104") (name "unconnected-(U1-PD2(INT0{slash}PCINT18)-Pad32)") (class "Default")
      (node (ref "U1") (pin "32") (pinfunction "PD2(INT0/PCINT18)_32") (pintype "bidirectional"))
    )
    (net (code "105") (name "unconnected-(U1-PE1-Pad6)") (class "Default")
      (node (ref "U1") (pin "6") (pinfunction "PE1_6") (pintype "bidirectional"))
    )
    (net (code "106") (name "unconnected-(U1-PE2(ADC6)-Pad19)") (class "Default")
      (node (ref "U1") (pin "19") (pinfunction "PE2(ADC6)_19") (pintype "bidirectional"))
    )
    (net (code "107") (name "unconnected-(U1-PE3(ADC7)-Pad22)") (class "Default")
      (node (ref "U1") (pin "22") (pinfunction "PE3(ADC7)_22") (pintype "bidirectional"))
    )
  )
)
